# 07_Memories.net
KiCad netlist of a schematic drawn in Altium Designer
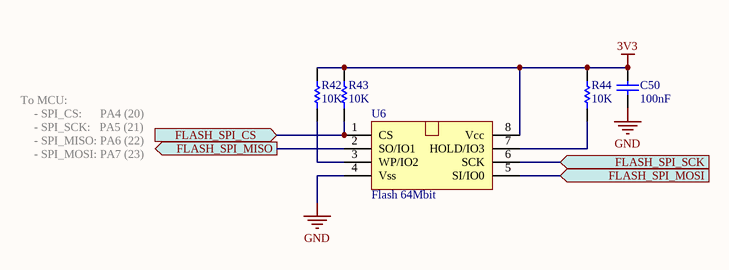
[diagram p0: 07 Memories.SchDoc]

(export (version "E")
  (design (tool "Eeschema 10.0.6"))
  (components
    (comp (ref "C50")
      (value "100nF")
      (footprint "0603 - C")
      (description "CAP CER 100nF 50V C0G/NP0 0603 ±5%")
      (fields (field (name "VOLTAGE") "50V") (field (name "MPN") "CL10C104JB8NNNC"))
      (libsource (lib "Library_Chip") (part "Cap 0603 100nF"))
    )
    (comp (ref "R42")
      (value "10K")
      (footprint "0603 - R")
      (description "RES SMD 10K OHM 1% 1/10W 0603")
      (fields (field (name "MFR") "Yageo") (field (name "MPN") "RC0603FR-0710KL"))
      (libsource (lib "Library_Chip") (part "Res 0603 10K"))
    )
    (comp (ref "R43")
      (value "10K")
      (footprint "0603 - R")
      (description "RES SMD 10K OHM 1% 1/10W 0603")
      (fields (field (name "MFR") "Yageo") (field (name "MPN") "RC0603FR-0710KL"))
      (libsource (lib "Library_Chip") (part "Res 0603 10K"))
    )
    (comp (ref "R44")
      (value "10K")
      (footprint "0603 - R")
      (description "RES SMD 10K OHM 1% 1/10W 0603")
      (fields (field (name "MFR") "Yageo") (field (name "MPN") "RC0603FR-0710KL"))
      (libsource (lib "Library_Chip") (part "Res 0603 10K"))
    )
    (comp (ref "U6")
      (value "Flash 64Mbit")
      (footprint "8 - SOIC")
      (description "IC FLASH 64MBIT CMOS SPI 8SOIC")
      (fields (field (name "MFR") "Cypress") (field (name "MPN") "S25FL164K0XMFI013"))
      (libsource (lib "Library_IC") (part "Flash 64Mb SOIC8"))
    )
  )
  (nets
    (net (code "1") (name "/FLASH_SPI_CS") (class "Default")
      (node (ref "R43") (pin "1") (pinfunction "1_1") (pintype "passive"))
      (node (ref "U6") (pin "1") (pinfunction "CS_1") (pintype "passive"))
    )
    (net (code "2") (name "/FLASH_SPI_MISO") (class "Default")
      (node (ref "U6") (pin "2") (pinfunction "SO/IO1_2") (pintype "passive"))
    )
    (net (code "3") (name "/FLASH_SPI_MOSI") (class "Default")
      (node (ref "U6") (pin "5") (pinfunction "SI/IO0_5") (pintype "passive"))
    )
    (net (code "4") (name "/FLASH_SPI_SCK") (class "Default")
      (node (ref "U6") (pin "6") (pinfunction "SCK_6") (pintype "passive"))
    )
    (net (code "5") (name "3V3") (class "Default")
      (node (ref "C50") (pin "2") (pinfunction "2_2") (pintype "passive"))
      (node (ref "R42") (pin "2") (pinfunction "2_2") (pintype "passive"))
      (node (ref "R43") (pin "2") (pinfunction "2_2") (pintype "passive"))
      (node (ref "R44") (pin "2") (pinfunction "2_2") (pintype "passive"))
      (node (ref "U6") (pin "8") (pinfunction "Vcc_8") (pintype "passive"))
    )
    (net (code "6") (name "GND") (class "Default")
      (node (ref "C50") (pin "1") (pinfunction "1_1") (pintype "passive"))
      (node (ref "U6") (pin "4") (pinfunction "Vss_4") (pintype "passive"))
    )
    (net (code "7") (name "Net-(U6-HOLD{slash}IO3)") (class "Default")
      (node (ref "R44") (pin "1") (pinfunction "1_1") (pintype "passive"))
      (node (ref "U6") (pin "7") (pinfunction "HOLD/IO3_7") (pintype "passive"))
    )
    (net (code "8") (name "Net-(U6-WP{slash}IO2)") (class "Default")
      (node (ref "R42") (pin "1") (pinfunction "1_1") (pintype "passive"))
      (node (ref "U6") (pin "3") (pinfunction "WP/IO2_3") (pintype "passive"))
    )
  )
)
